# Buzzer.net
KiCad netlist of a schematic drawn in Altium Designer
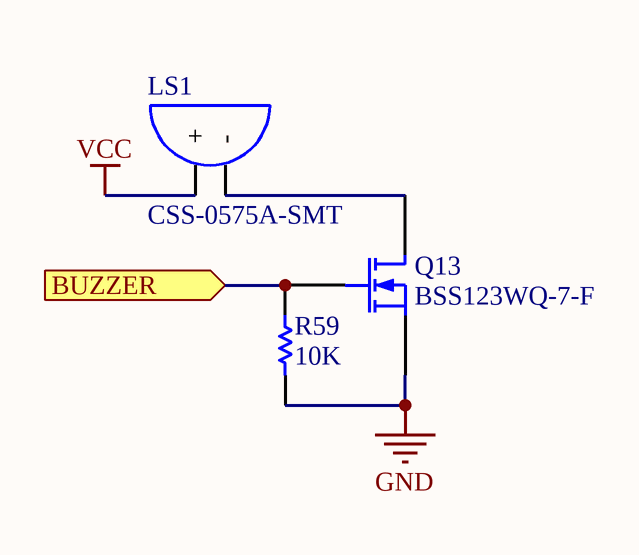
[diagram p0: Buzzer.SchDoc]

(export (version "E")
  (design (tool "Eeschema 10.0.6"))
  (components
    (comp (ref "LS1")
      (value "CSS-0575A-SMT")
      (footprint "CSS-0575A-SMT")
      (description "Magnetic Buzzer Transducer")
      (fields (field (name "MANUFACTURER") "CUI, Inc."))
      (libsource (lib "Components") (part "CSS-0575A-SMT"))
    )
    (comp (ref "Q13")
      (value "BSS123WQ-7-F")
      (footprint "SOT323-3")
      (description "N-Channel MOSFET")
      (fields (field (name "MANUFACTURER") "Diodes Incorporated"))
      (libsource (lib "MOSFETs") (part "BSS123WQ-7-F"))
    )
    (comp (ref "R59")
      (value "10K")
      (footprint "R0603[1608]")
      (description "10K 0.25W 1% 0603 (1005 Metric)")
      (fields (field (name "MANUFACTURER") "Vishay") (field (name "PARTNUMBER") "RCS060310K0FKEA"))
      (libsource (lib "Resistors") (part "RES_10K_0603_1%"))
    )
  )
  (nets
    (net (code "1") (name "/BUZZER") (class "Default")
      (node (ref "Q13") (pin "1") (pinfunction "G_1") (pintype "passive"))
      (node (ref "R59") (pin "2") (pinfunction "2_2") (pintype "passive"))
    )
    (net (code "2") (name "GND") (class "Default")
      (node (ref "Q13") (pin "2") (pinfunction "S_2") (pintype "passive"))
      (node (ref "R59") (pin "1") (pinfunction "1_1") (pintype "passive"))
    )
    (net (code "3") (name "Net-(LS1--)") (class "Default")
      (node (ref "LS1") (pin "2") (pinfunction "-_2") (pintype "passive"))
      (node (ref "Q13") (pin "3") (pinfunction "D_3") (pintype "passive"))
    )
    (net (code "4") (name "VCC") (class "Default")
      (node (ref "LS1") (pin "1") (pinfunction "+_1") (pintype "passive"))
    )
  )
)
